# FingerPrint_TS.net
KiCad netlist of a schematic drawn in Altium Designer
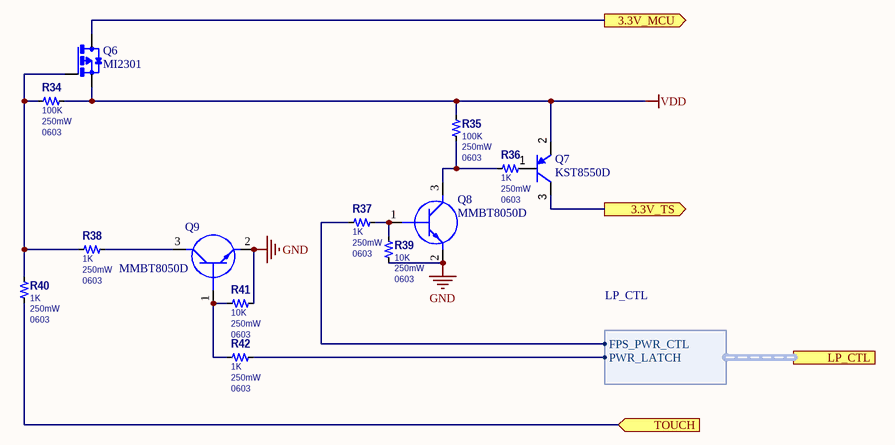
[diagram p0: FingerPrint_TS.SchDoc]

(export (version "E")
  (design (tool "Eeschema 10.0.6"))
  (components
    (comp (ref "Q6") (value "MI2301") (footprint "SOT23") (libsource (lib "Safety_Lock") (part "MI2301")))
    (comp (ref "Q7")
      (value "KST8550D")
      (footprint "SOT23")
      (description "Trans GP BJT PNP 45V 0.5A 350mW Automotive 3-Pin SOT-23 T/R")
      (fields (field (name "MANUFACTURER") "Diodes"))
      (libsource (lib "Safety_Lock") (part "KST8550D"))
    )
    (comp (ref "Q8")
      (value "MMBT8050D")
      (footprint "SOT23")
      (description "Transistor BJT NPN")
      (fields (field (name "MANUFACTURER_PART_NUMBER") "MMBT8050"))
      (libsource (lib "Safety_Lock") (part "MMBT8050D"))
    )
    (comp (ref "Q9")
      (value "MMBT8050D")
      (footprint "SOT23")
      (description "Transistor BJT NPN")
      (fields (field (name "MANUFACTURER_PART_NUMBER") "MMBT8050"))
      (libsource (lib "Safety_Lock") (part "MMBT8050D"))
    )
    (comp (ref "R34")
      (value "100K")
      (footprint "0603-R")
      (fields
        (field (name "MANUFACTURER") "Panasonic")
        (field (name "MANUFACTURER PART NUMBER") "ERJ-8GEYJ621V")
        (field (name "TOLERANCE") "5%")
        (field (name "POWER RATING") "250mW")
        (field (name "CASE/PACKAGE") "0603")
      )
      (libsource (lib "Safety_Lock") (part "Res"))
    )
    (comp (ref "R35")
      (value "100K")
      (footprint "0603-R")
      (fields
        (field (name "MANUFACTURER") "Panasonic")
        (field (name "MANUFACTURER PART NUMBER") "ERJ-8GEYJ621V")
        (field (name "TOLERANCE") "5%")
        (field (name "POWER RATING") "250mW")
        (field (name "CASE/PACKAGE") "0603")
      )
      (libsource (lib "Safety_Lock") (part "Res"))
    )
    (comp (ref "R36")
      (value "1K")
      (footprint "0603-R")
      (fields
        (field (name "MANUFACTURER") "Panasonic")
        (field (name "MANUFACTURER PART NUMBER") "ERJ-8GEYJ621V")
        (field (name "TOLERANCE") "5%")
        (field (name "POWER RATING") "250mW")
        (field (name "CASE/PACKAGE") "0603")
      )
      (libsource (lib "Safety_Lock") (part "Res"))
    )
    (comp (ref "R37")
      (value "1K")
      (footprint "0603-R")
      (fields
        (field (name "MANUFACTURER") "Panasonic")
        (field (name "MANUFACTURER PART NUMBER") "ERJ-8GEYJ621V")
        (field (name "TOLERANCE") "5%")
        (field (name "POWER RATING") "250mW")
        (field (name "CASE/PACKAGE") "0603")
      )
      (libsource (lib "Safety_Lock") (part "Res"))
    )
    (comp (ref "R38")
      (value "1K")
      (footprint "0603-R")
      (fields
        (field (name "MANUFACTURER") "Panasonic")
        (field (name "MANUFACTURER PART NUMBER") "ERJ-8GEYJ621V")
        (field (name "TOLERANCE") "5%")
        (field (name "POWER RATING") "250mW")
        (field (name "CASE/PACKAGE") "0603")
      )
      (libsource (lib "Safety_Lock") (part "Res"))
    )
    (comp (ref "R39")
      (value "10K")
      (footprint "0603-R")
      (fields
        (field (name "MANUFACTURER") "Panasonic")
        (field (name "MANUFACTURER PART NUMBER") "ERJ-8GEYJ621V")
        (field (name "TOLERANCE") "5%")
        (field (name "POWER RATING") "250mW")
        (field (name "CASE/PACKAGE") "0603")
      )
      (libsource (lib "Safety_Lock") (part "Res"))
    )
    (comp (ref "R40")
      (value "1K")
      (footprint "0603-R")
      (fields
        (field (name "MANUFACTURER") "Panasonic")
        (field (name "MANUFACTURER PART NUMBER") "ERJ-8GEYJ621V")
        (field (name "TOLERANCE") "5%")
        (field (name "POWER RATING") "250mW")
        (field (name "CASE/PACKAGE") "0603")
      )
      (libsource (lib "Safety_Lock") (part "Res"))
    )
    (comp (ref "R41")
      (value "10K")
      (footprint "0603-R")
      (fields
        (field (name "MANUFACTURER") "Panasonic")
        (field (name "MANUFACTURER PART NUMBER") "ERJ-8GEYJ621V")
        (field (name "TOLERANCE") "5%")
        (field (name "POWER RATING") "250mW")
        (field (name "CASE/PACKAGE") "0603")
      )
      (libsource (lib "Safety_Lock") (part "Res"))
    )
    (comp (ref "R42")
      (value "1K")
      (footprint "0603-R")
      (fields
        (field (name "MANUFACTURER") "Panasonic")
        (field (name "MANUFACTURER PART NUMBER") "ERJ-8GEYJ621V")
        (field (name "TOLERANCE") "5%")
        (field (name "POWER RATING") "250mW")
        (field (name "CASE/PACKAGE") "0603")
      )
      (libsource (lib "Safety_Lock") (part "Res"))
    )
  )
  (nets
    (net (code "2") (name "/3.3V_MCU") (class "Default")
      (node (ref "Q6") (pin "3") (pinfunction "D_3") (pintype "passive"))
    )
    (net (code "3") (name "/3.3V_TS") (class "Default")
      (node (ref "Q7") (pin "3") (pinfunction "Collector_3") (pintype "passive"))
    )
    (net (code "4") (name "/FPS_PWR_CTL") (class "Default")
      (node (ref "R37") (pin "1") (pinfunction "1_1") (pintype "passive"))
    )
    (net (code "5") (name "/PWR_LATCH") (class "Default")
      (node (ref "R42") (pin "1") (pinfunction "1_1") (pintype "passive"))
    )
    (net (code "6") (name "/TOUCH") (class "Default")
      (node (ref "R40") (pin "1") (pinfunction "1_1") (pintype "passive"))
    )
    (net (code "8") (name "GND") (class "Default")
      (node (ref "Q8") (pin "2") (pinfunction "E_2") (pintype "passive"))
      (node (ref "Q9") (pin "2") (pinfunction "E_2") (pintype "passive"))
      (node (ref "R39") (pin "1") (pinfunction "1_1") (pintype "passive"))
      (node (ref "R41") (pin "2") (pinfunction "2_2") (pintype "passive"))
    )
    (net (code "9") (name "Net-(Q6-G)") (class "Default")
      (node (ref "Q6") (pin "1") (pinfunction "G_1") (pintype "passive"))
      (node (ref "R34") (pin "2") (pinfunction "2_2") (pintype "passive"))
      (node (ref "R38") (pin "1") (pinfunction "1_1") (pintype "passive"))
      (node (ref "R40") (pin "2") (pinfunction "2_2") (pintype "passive"))
    )
    (net (code "10") (name "Net-(Q7-Base)") (class "Default")
      (node (ref "Q7") (pin "1") (pinfunction "Base_1") (pintype "passive"))
      (node (ref "R36") (pin "2") (pinfunction "2_2") (pintype "passive"))
    )
    (net (code "11") (name "Net-(Q8-B)") (class "Default")
      (node (ref "Q8") (pin "1") (pinfunction "B_1") (pintype "passive"))
      (node (ref "R37") (pin "2") (pinfunction "2_2") (pintype "passive"))
      (node (ref "R39") (pin "2") (pinfunction "2_2") (pintype "passive"))
    )
    (net (code "12") (name "Net-(Q8-C)") (class "Default")
      (node (ref "Q8") (pin "3") (pinfunction "C_3") (pintype "passive"))
      (node (ref "R35") (pin "1") (pinfunction "1_1") (pintype "passive"))
      (node (ref "R36") (pin "1") (pinfunction "1_1") (pintype "passive"))
    )
    (net (code "13") (name "Net-(Q9-B)") (class "Default")
      (node (ref "Q9") (pin "1") (pinfunction "B_1") (pintype "passive"))
      (node (ref "R41") (pin "1") (pinfunction "1_1") (pintype "passive"))
      (node (ref "R42") (pin "2") (pinfunction "2_2") (pintype "passive"))
    )
    (net (code "14") (name "Net-(Q9-C)") (class "Default")
      (node (ref "Q9") (pin "3") (pinfunction "C_3") (pintype "passive"))
      (node (ref "R38") (pin "2") (pinfunction "2_2") (pintype "passive"))
    )
    (net (code "15") (name "VDD") (class "Default")
      (node (ref "Q6") (pin "2") (pinfunction "S_2") (pintype "passive"))
      (node (ref "Q7") (pin "2") (pinfunction "Emitter_2") (pintype "passive"))
      (node (ref "R34") (pin "1") (pinfunction "1_1") (pintype "passive"))
      (node (ref "R35") (pin "2") (pinfunction "2_2") (pintype "passive"))
    )
  )
)
